# ethernet-phy.net
KiCad netlist of a schematic drawn in Altium Designer
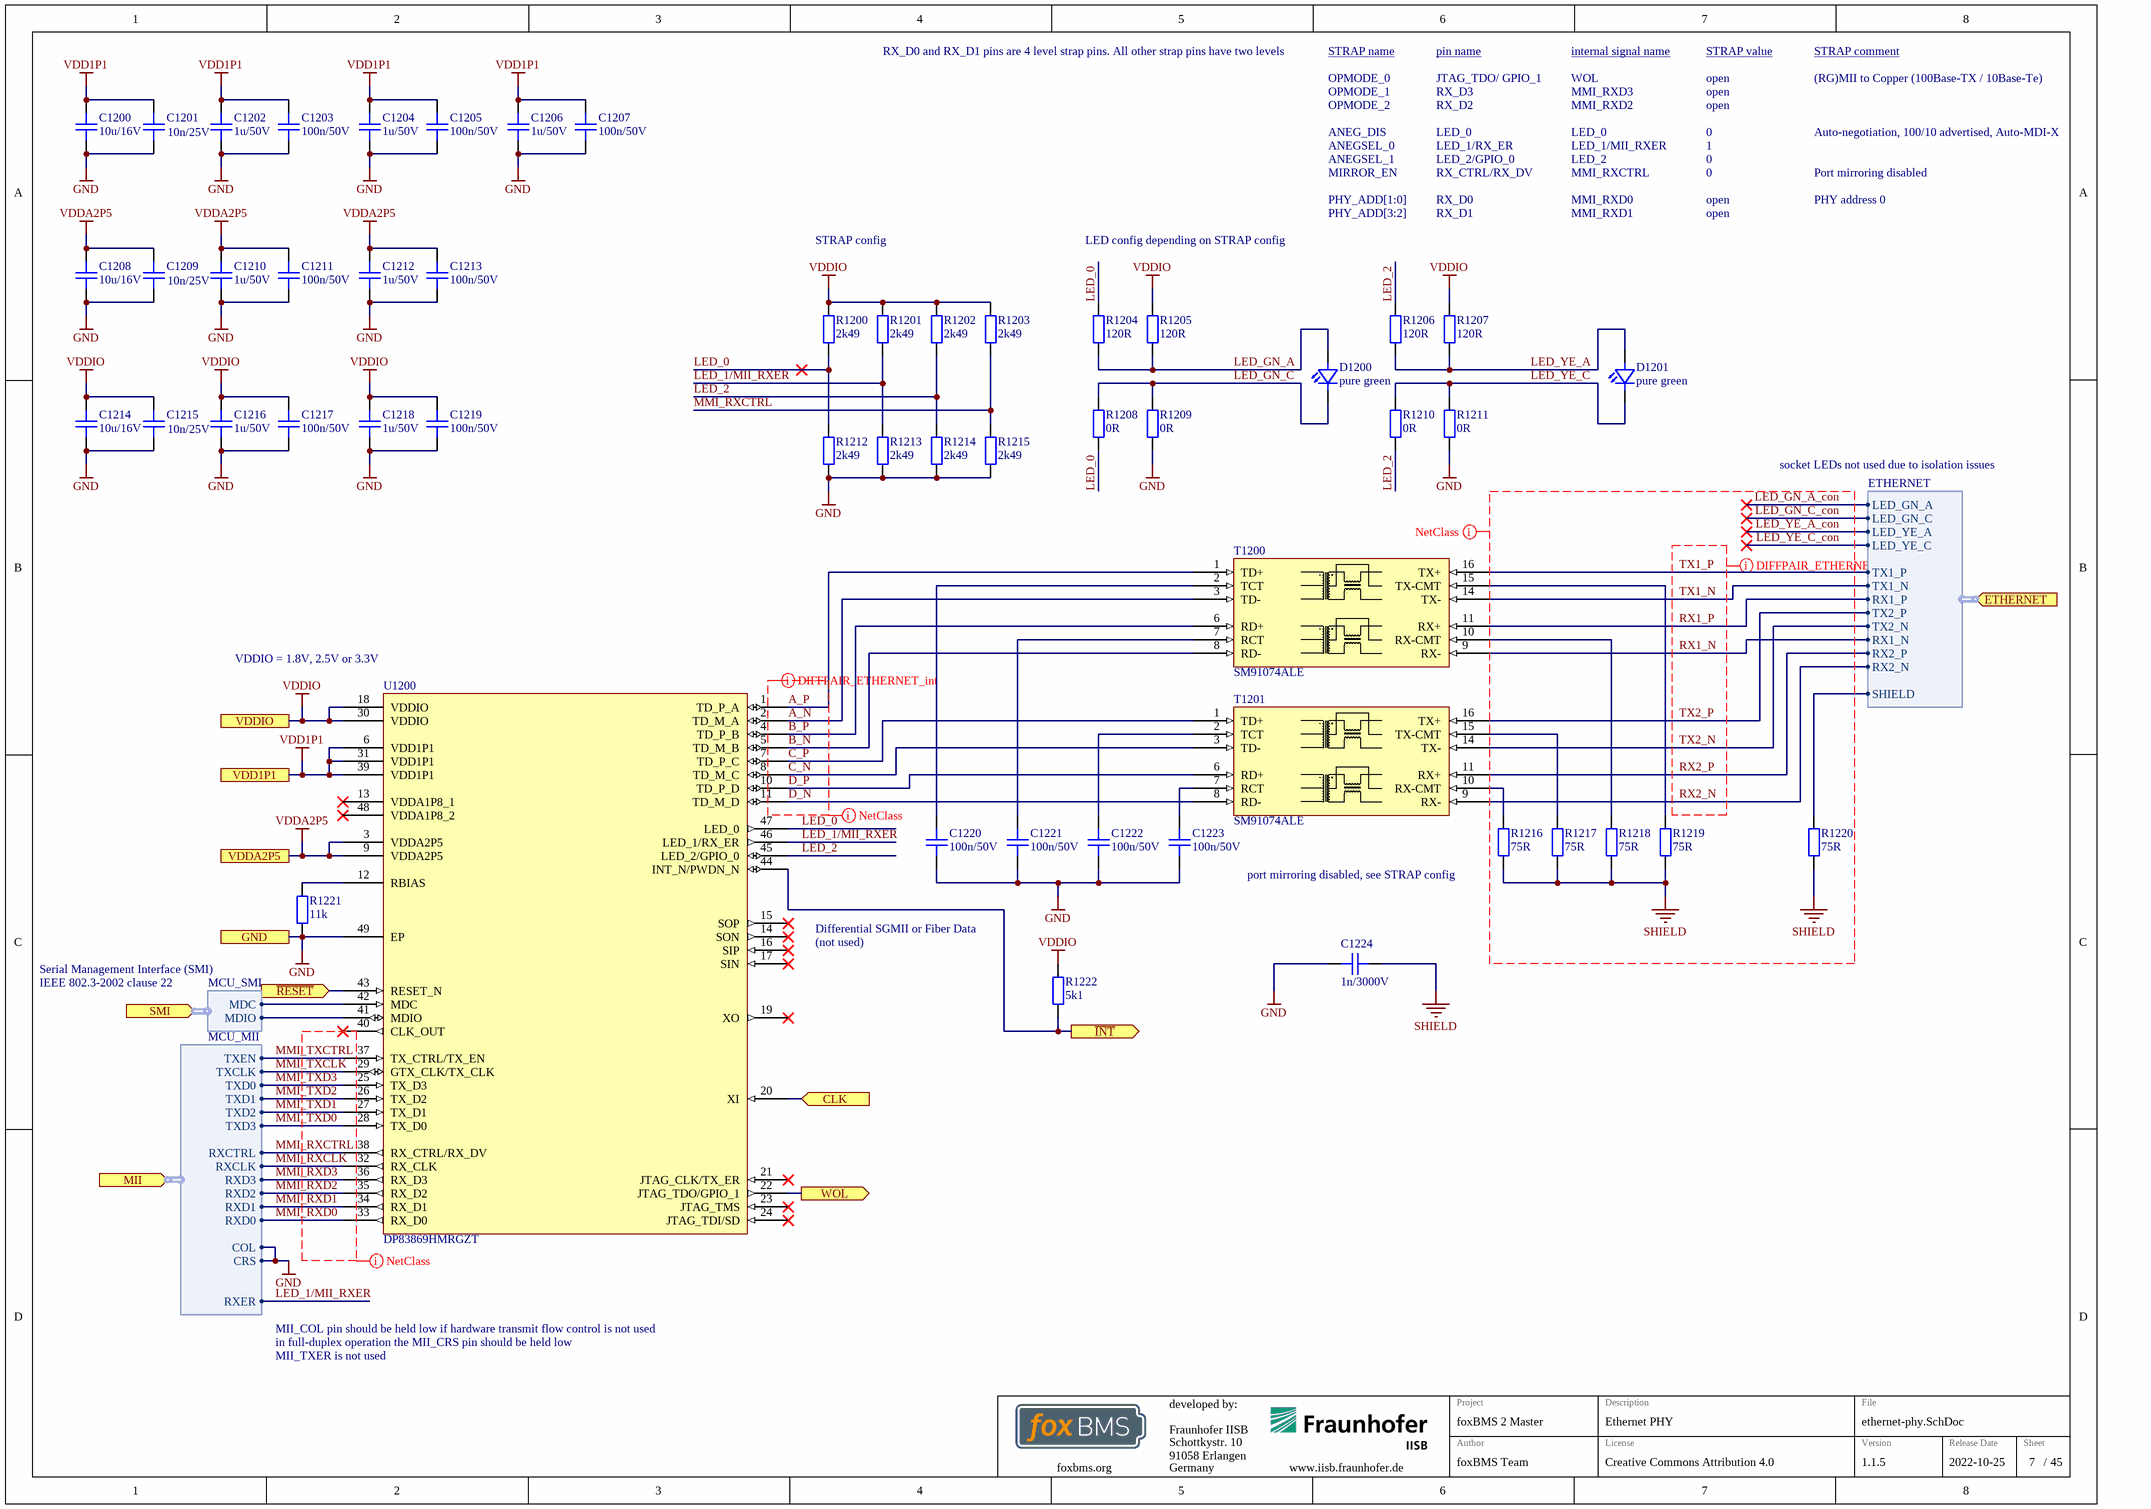
[diagram p0: ethernet-phy.SchDoc]

(export (version "E")
  (design (tool "Eeschema 10.0.6"))
  (components
    (comp (ref "C1200")
      (value "10u/16V")
      (footprint "CAPC2012X14N")
      (description "MLCC")
      (fields (field (name "PART NUMBER") "gen_C_ceramic_10u_16V_X7R_0805"))
      (libsource (lib "OE750") (part "C"))
    )
    (comp (ref "C1201")
      (value "10n/25V")
      (footprint "CAPC1005X06N")
      (description "MLCC")
      (fields (field (name "PART NUMBER") "gen_C_ceramic_10n_25V_X7R_0402"))
      (libsource (lib "OE750") (part "C"))
    )
    (comp (ref "C1202")
      (value "1u/50V")
      (footprint "CAPC1608X08N")
      (description "MLCC")
      (fields (field (name "PART NUMBER") "gen_C_ceramic_1u_50V_X7R_0603") (field (name "TOLERANCE") "± 10%"))
      (libsource (lib "OE750") (part "C"))
    )
    (comp (ref "C1203")
      (value "100n/50V")
      (footprint "CAPC1005X06N")
      (description "MLCC")
      (fields (field (name "PART NUMBER") "gen_C_ceramic_100n_50V_X7R_0402"))
      (libsource (lib "OE750") (part "C"))
    )
    (comp (ref "C1204")
      (value "1u/50V")
      (footprint "CAPC1608X08N")
      (description "MLCC")
      (fields (field (name "PART NUMBER") "gen_C_ceramic_1u_50V_X7R_0603") (field (name "TOLERANCE") "± 10%"))
      (libsource (lib "OE750") (part "C"))
    )
    (comp (ref "C1205")
      (value "100n/50V")
      (footprint "CAPC1005X06N")
      (description "MLCC")
      (fields (field (name "PART NUMBER") "gen_C_ceramic_100n_50V_X7R_0402"))
      (libsource (lib "OE750") (part "C"))
    )
    (comp (ref "C1206")
      (value "1u/50V")
      (footprint "CAPC1608X08N")
      (description "MLCC")
      (fields (field (name "PART NUMBER") "gen_C_ceramic_1u_50V_X7R_0603") (field (name "TOLERANCE") "± 10%"))
      (libsource (lib "OE750") (part "C"))
    )
    (comp (ref "C1207")
      (value "100n/50V")
      (footprint "CAPC1005X06N")
      (description "MLCC")
      (fields (field (name "PART NUMBER") "gen_C_ceramic_100n_50V_X7R_0402"))
      (libsource (lib "OE750") (part "C"))
    )
    (comp (ref "C1208")
      (value "10u/16V")
      (footprint "CAPC2012X14N")
      (description "MLCC")
      (fields (field (name "PART NUMBER") "gen_C_ceramic_10u_16V_X7R_0805"))
      (libsource (lib "OE750") (part "C"))
    )
    (comp (ref "C1209")
      (value "10n/25V")
      (footprint "CAPC1005X06N")
      (description "MLCC")
      (fields (field (name "PART NUMBER") "gen_C_ceramic_10n_25V_X7R_0402"))
      (libsource (lib "OE750") (part "C"))
    )
    (comp (ref "C1210")
      (value "1u/50V")
      (footprint "CAPC1608X08N")
      (description "MLCC")
      (fields (field (name "PART NUMBER") "gen_C_ceramic_1u_50V_X7R_0603") (field (name "TOLERANCE") "± 10%"))
      (libsource (lib "OE750") (part "C"))
    )
    (comp (ref "C1211")
      (value "100n/50V")
      (footprint "CAPC1005X06N")
      (description "MLCC")
      (fields (field (name "PART NUMBER") "gen_C_ceramic_100n_50V_X7R_0402"))
      (libsource (lib "OE750") (part "C"))
    )
    (comp (ref "C1212")
      (value "1u/50V")
      (footprint "CAPC1608X08N")
      (description "MLCC")
      (fields (field (name "PART NUMBER") "gen_C_ceramic_1u_50V_X7R_0603") (field (name "TOLERANCE") "± 10%"))
      (libsource (lib "OE750") (part "C"))
    )
    (comp (ref "C1213")
      (value "100n/50V")
      (footprint "CAPC1005X06N")
      (description "MLCC")
      (fields (field (name "PART NUMBER") "gen_C_ceramic_100n_50V_X7R_0402"))
      (libsource (lib "OE750") (part "C"))
    )
    (comp (ref "C1214")
      (value "10u/16V")
      (footprint "CAPC2012X14N")
      (description "MLCC")
      (fields (field (name "PART NUMBER") "gen_C_ceramic_10u_16V_X7R_0805"))
      (libsource (lib "OE750") (part "C"))
    )
    (comp (ref "C1215")
      (value "10n/25V")
      (footprint "CAPC1005X06N")
      (description "MLCC")
      (fields (field (name "PART NUMBER") "gen_C_ceramic_10n_25V_X7R_0402"))
      (libsource (lib "OE750") (part "C"))
    )
    (comp (ref "C1216")
      (value "1u/50V")
      (footprint "CAPC1608X08N")
      (description "MLCC")
      (fields (field (name "PART NUMBER") "gen_C_ceramic_1u_50V_X7R_0603") (field (name "TOLERANCE") "± 10%"))
      (libsource (lib "OE750") (part "C"))
    )
    (comp (ref "C1217")
      (value "100n/50V")
      (footprint "CAPC1005X06N")
      (description "MLCC")
      (fields (field (name "PART NUMBER") "gen_C_ceramic_100n_50V_X7R_0402"))
      (libsource (lib "OE750") (part "C"))
    )
    (comp (ref "C1218")
      (value "1u/50V")
      (footprint "CAPC1608X08N")
      (description "MLCC")
      (fields (field (name "PART NUMBER") "gen_C_ceramic_1u_50V_X7R_0603") (field (name "TOLERANCE") "± 10%"))
      (libsource (lib "OE750") (part "C"))
    )
    (comp (ref "C1219")
      (value "100n/50V")
      (footprint "CAPC1005X06N")
      (description "MLCC")
      (fields (field (name "PART NUMBER") "gen_C_ceramic_100n_50V_X7R_0402"))
      (libsource (lib "OE750") (part "C"))
    )
    (comp (ref "C1220")
      (value "100n/50V")
      (footprint "CAPC1005X06N")
      (description "MLCC")
      (fields (field (name "PART NUMBER") "gen_C_ceramic_100n_50V_X7R_0402"))
      (libsource (lib "OE750") (part "C"))
    )
    (comp (ref "C1221")
      (value "100n/50V")
      (footprint "CAPC1005X06N")
      (description "MLCC")
      (fields (field (name "PART NUMBER") "gen_C_ceramic_100n_50V_X7R_0402"))
      (libsource (lib "OE750") (part "C"))
    )
    (comp (ref "C1222")
      (value "100n/50V")
      (footprint "CAPC1005X06N")
      (description "MLCC")
      (fields (field (name "PART NUMBER") "gen_C_ceramic_100n_50V_X7R_0402"))
      (libsource (lib "OE750") (part "C"))
    )
    (comp (ref "C1223")
      (value "100n/50V")
      (footprint "CAPC1005X06N")
      (description "MLCC")
      (fields (field (name "PART NUMBER") "gen_C_ceramic_100n_50V_X7R_0402"))
      (libsource (lib "OE750") (part "C"))
    )
    (comp (ref "C1224")
      (value "1n/3000V")
      (footprint "CAPC2220(5750)230_N")
      (description "MLCC")
      (fields (field (name "PART NUMBER") "gen_C_ceramic_1n_3000V_X7R_2220"))
      (libsource (lib "OE750") (part "C"))
    )
    (comp (ref "D1200")
      (value "pure green")
      (footprint "LEDC1608X07N")
      (description "TLMP1100-GS08")
      (fields (field (name "PART NUMBER") "LED_0603_pure_green_AECQ") (field (name "MANUFACTURER") "Vishay"))
      (libsource (lib "OE750") (part "D_LED"))
    )
    (comp (ref "D1201")
      (value "pure green")
      (footprint "LEDC1608X07N")
      (description "TLMP1100-GS08")
      (fields (field (name "PART NUMBER") "LED_0603_pure_green_AECQ") (field (name "MANUFACTURER") "Vishay"))
      (libsource (lib "OE750") (part "D_LED"))
    )
    (comp (ref "R1200")
      (value "2k49")
      (footprint "RESC1005X04N")
      (description "SMD Resistor 2k49 0402")
      (fields (field (name "PART NUMBER") "gen_R_2k49_0402") (field (name "TOLERANCE") "1%"))
      (libsource (lib "OE750") (part "R"))
    )
    (comp (ref "R1201")
      (value "2k49")
      (footprint "RESC1005X04N")
      (description "SMD Resistor 2k49 0402")
      (fields (field (name "PART NUMBER") "gen_R_2k49_0402") (field (name "TOLERANCE") "1%"))
      (libsource (lib "OE750") (part "R"))
    )
    (comp (ref "R1202")
      (value "2k49")
      (footprint "RESC1005X04N")
      (description "SMD Resistor 2k49 0402")
      (fields (field (name "PART NUMBER") "gen_R_2k49_0402") (field (name "TOLERANCE") "1%"))
      (libsource (lib "OE750") (part "R"))
    )
    (comp (ref "R1203")
      (value "2k49")
      (footprint "RESC1005X04N")
      (description "SMD Resistor 2k49 0402")
      (fields (field (name "PART NUMBER") "gen_R_2k49_0402") (field (name "TOLERANCE") "1%"))
      (libsource (lib "OE750") (part "R"))
    )
    (comp (ref "R1204")
      (value "120R")
      (footprint "RESC1005X04N")
      (description "SMD Resistor 120R 0402")
      (fields (field (name "PART NUMBER") "gen_R_120R_0402") (field (name "TOLERANCE") "1%"))
      (libsource (lib "OE750") (part "R"))
    )
    (comp (ref "R1205")
      (value "120R")
      (footprint "RESC1005X04N")
      (description "SMD Resistor 120R 0402")
      (fields (field (name "PART NUMBER") "gen_R_120R_0402") (field (name "TOLERANCE") "1%"))
      (libsource (lib "OE750") (part "R"))
    )
    (comp (ref "R1206")
      (value "120R")
      (footprint "RESC1005X04N")
      (description "SMD Resistor 120R 0402")
      (fields (field (name "PART NUMBER") "gen_R_120R_0402") (field (name "TOLERANCE") "1%"))
      (libsource (lib "OE750") (part "R"))
    )
    (comp (ref "R1207")
      (value "120R")
      (footprint "RESC1005X04N")
      (description "SMD Resistor 120R 0402")
      (fields (field (name "PART NUMBER") "gen_R_120R_0402") (field (name "TOLERANCE") "1%"))
      (libsource (lib "OE750") (part "R"))
    )
    (comp (ref "R1208")
      (value "0R")
      (footprint "RESC1005X04N")
      (description "SMD Resistor 0R 0402")
      (fields (field (name "PART NUMBER") "gen_R_0R_0402") (field (name "POWER") "0.063W"))
      (libsource (lib "OE750") (part "R"))
    )
    (comp (ref "R1209")
      (value "0R")
      (footprint "RESC1005X04N")
      (description "SMD Resistor 0R 0402")
      (fields (field (name "PART NUMBER") "gen_R_0R_0402") (field (name "POWER") "0.063W"))
      (libsource (lib "OE750") (part "R"))
    )
    (comp (ref "R1210")
      (value "0R")
      (footprint "RESC1005X04N")
      (description "SMD Resistor 0R 0402")
      (fields (field (name "PART NUMBER") "gen_R_0R_0402") (field (name "POWER") "0.063W"))
      (libsource (lib "OE750") (part "R"))
    )
    (comp (ref "R1211")
      (value "0R")
      (footprint "RESC1005X04N")
      (description "SMD Resistor 0R 0402")
      (fields (field (name "PART NUMBER") "gen_R_0R_0402") (field (name "POWER") "0.063W"))
      (libsource (lib "OE750") (part "R"))
    )
    (comp (ref "R1212")
      (value "2k49")
      (footprint "RESC1005X04N")
      (description "SMD Resistor 2k49 0402")
      (fields (field (name "PART NUMBER") "gen_R_2k49_0402") (field (name "TOLERANCE") "1%"))
      (libsource (lib "OE750") (part "R"))
    )
    (comp (ref "R1213")
      (value "2k49")
      (footprint "RESC1005X04N")
      (description "SMD Resistor 2k49 0402")
      (fields (field (name "PART NUMBER") "gen_R_2k49_0402") (field (name "TOLERANCE") "1%"))
      (libsource (lib "OE750") (part "R"))
    )
    (comp (ref "R1214")
      (value "2k49")
      (footprint "RESC1005X04N")
      (description "SMD Resistor 2k49 0402")
      (fields (field (name "PART NUMBER") "gen_R_2k49_0402") (field (name "TOLERANCE") "1%"))
      (libsource (lib "OE750") (part "R"))
    )
    (comp (ref "R1215")
      (value "2k49")
      (footprint "RESC1005X04N")
      (description "SMD Resistor 2k49 0402")
      (fields (field (name "PART NUMBER") "gen_R_2k49_0402") (field (name "TOLERANCE") "1%"))
      (libsource (lib "OE750") (part "R"))
    )
    (comp (ref "R1216")
      (value "75R")
      (footprint "RESC1005X04N")
      (description "SMD Resistor 75R 0402")
      (fields (field (name "PART NUMBER") "gen_R_75R_0402") (field (name "TOLERANCE") "1%"))
      (libsource (lib "OE750") (part "R"))
    )
    (comp (ref "R1217")
      (value "75R")
      (footprint "RESC1005X04N")
      (description "SMD Resistor 75R 0402")
      (fields (field (name "PART NUMBER") "gen_R_75R_0402") (field (name "TOLERANCE") "1%"))
      (libsource (lib "OE750") (part "R"))
    )
    (comp (ref "R1218")
      (value "75R")
      (footprint "RESC1005X04N")
      (description "SMD Resistor 75R 0402")
      (fields (field (name "PART NUMBER") "gen_R_75R_0402") (field (name "TOLERANCE") "1%"))
      (libsource (lib "OE750") (part "R"))
    )
    (comp (ref "R1219")
      (value "75R")
      (footprint "RESC1005X04N")
      (description "SMD Resistor 75R 0402")
      (fields (field (name "PART NUMBER") "gen_R_75R_0402") (field (name "TOLERANCE") "1%"))
      (libsource (lib "OE750") (part "R"))
    )
    (comp (ref "R1220")
      (value "75R")
      (footprint "RESC1005X04N")
      (description "SMD Resistor 75R 0402")
      (fields (field (name "PART NUMBER") "gen_R_75R_0402") (field (name "TOLERANCE") "1%"))
      (libsource (lib "OE750") (part "R"))
    )
    (comp (ref "R1221")
      (value "11k")
      (footprint "RESC1005X04N")
      (description "SMD Resistor 11k 0402")
      (fields (field (name "PART NUMBER") "gen_R_11k_0402") (field (name "TOLERANCE") "1%"))
      (libsource (lib "OE750") (part "R"))
    )
    (comp (ref "R1222")
      (value "5k1")
      (footprint "RESC1005X04N")
      (description "SMD Resistor 5k1 0402")
      (fields (field (name "PART NUMBER") "gen_R_5k1_0402") (field (name "TOLERANCE") "1%"))
      (libsource (lib "OE750") (part "R"))
    )
    (comp (ref "T1200")
      (value "SM91074ALE")
      (footprint "SM91074ALE")
      (description "10/100 Base-T Transformer")
      (fields (field (name "MANUFACTURER") "Bourns"))
      (libsource (lib "OE750") (part "SM91074ALE"))
    )
    (comp (ref "T1201")
      (value "SM91074ALE")
      (footprint "SM91074ALE")
      (description "10/100 Base-T Transformer")
      (fields (field (name "MANUFACTURER") "Bourns"))
      (libsource (lib "OE750") (part "SM91074ALE"))
    )
    (comp (ref "U1200")
      (value "DP83869HMRGZT")
      (footprint "DP83869HM-RGZ")
      (description "High Immunity 10/100/1000 Ethernet Physical Layer Transceiver and Fiber Interface")
      (fields (field (name "MANUFACTURER") "Texas Instruments"))
      (libsource (lib "OE750") (part "DP83869HM"))
    )
  )
  (nets
    (net (code "4") (name "/A_N") (class "Default")
      (node (ref "T1200") (pin "3") (pinfunction "TD-_3") (pintype "input"))
      (node (ref "U1200") (pin "2") (pinfunction "TD_M_A_2") (pintype "bidirectional"))
    )
    (net (code "5") (name "/A_P") (class "Default")
      (node (ref "T1200") (pin "1") (pinfunction "TD+_1") (pintype "input"))
      (node (ref "U1200") (pin "1") (pinfunction "TD_P_A_1") (pintype "bidirectional"))
    )
    (net (code "6") (name "/B_N") (class "Default")
      (node (ref "T1200") (pin "8") (pinfunction "RD-_8") (pintype "input"))
      (node (ref "U1200") (pin "5") (pinfunction "TD_M_B_5") (pintype "bidirectional"))
    )
    (net (code "7") (name "/B_P") (class "Default")
      (node (ref "T1200") (pin "6") (pinfunction "RD+_6") (pintype "input"))
      (node (ref "U1200") (pin "4") (pinfunction "TD_P_B_4") (pintype "bidirectional"))
    )
    (net (code "8") (name "/CLK") (class "Default")
      (node (ref "U1200") (pin "20") (pinfunction "XI_20") (pintype "input"))
    )
    (net (code "9") (name "/C_N") (class "Default")
      (node (ref "T1201") (pin "3") (pinfunction "TD-_3") (pintype "input"))
      (node (ref "U1200") (pin "8") (pinfunction "TD_M_C_8") (pintype "bidirectional"))
    )
    (net (code "10") (name "/C_P") (class "Default")
      (node (ref "T1201") (pin "1") (pinfunction "TD+_1") (pintype "input"))
      (node (ref "U1200") (pin "7") (pinfunction "TD_P_C_7") (pintype "bidirectional"))
    )
    (net (code "11") (name "/D_N") (class "Default")
      (node (ref "T1201") (pin "8") (pinfunction "RD-_8") (pintype "input"))
      (node (ref "U1200") (pin "11") (pinfunction "TD_M_D_11") (pintype "bidirectional"))
    )
    (net (code "12") (name "/D_P") (class "Default")
      (node (ref "T1201") (pin "6") (pinfunction "RD+_6") (pintype "input"))
      (node (ref "U1200") (pin "10") (pinfunction "TD_P_D_10") (pintype "bidirectional"))
    )
    (net (code "13") (name "/INT") (class "Default")
      (node (ref "R1222") (pin "1") (pinfunction "1_1") (pintype "passive"))
      (node (ref "U1200") (pin "44") (pinfunction "INT_N/PWDN_N_44") (pintype "bidirectional"))
    )
    (net (code "14") (name "/LED_0") (class "Default")
      (node (ref "R1200") (pin "1") (pinfunction "1_1") (pintype "passive"))
      (node (ref "R1204") (pin "2") (pinfunction "2_2") (pintype "passive"))
      (node (ref "R1208") (pin "1") (pinfunction "1_1") (pintype "passive"))
      (node (ref "R1212") (pin "2") (pinfunction "2_2") (pintype "passive"))
      (node (ref "U1200") (pin "47") (pinfunction "LED_0_47") (pintype "output"))
    )
    (net (code "15") (name "/LED_1{slash}MII_RXER") (class "Default")
      (node (ref "R1201") (pin "1") (pinfunction "1_1") (pintype "passive"))
      (node (ref "R1213") (pin "2") (pinfunction "2_2") (pintype "passive"))
      (node (ref "U1200") (pin "46") (pinfunction "LED_1/RX_ER_46") (pintype "output"))
    )
    (net (code "16") (name "/LED_2") (class "Default")
      (node (ref "R1202") (pin "1") (pinfunction "1_1") (pintype "passive"))
      (node (ref "R1206") (pin "2") (pinfunction "2_2") (pintype "passive"))
      (node (ref "R1210") (pin "1") (pinfunction "1_1") (pintype "passive"))
      (node (ref "R1214") (pin "2") (pinfunction "2_2") (pintype "passive"))
      (node (ref "U1200") (pin "45") (pinfunction "LED_2/GPIO_0_45") (pintype "bidirectional"))
    )
    (net (code "17") (name "/LED_GN_A") (class "Default")
      (node (ref "D1200") (pin "2") (pinfunction "A_2") (pintype "passive"))
      (node (ref "R1204") (pin "1") (pinfunction "1_1") (pintype "passive"))
      (node (ref "R1205") (pin "1") (pinfunction "1_1") (pintype "passive"))
    )
    (net (code "19") (name "/LED_GN_C") (class "Default")
      (node (ref "D1200") (pin "1") (pinfunction "C_1") (pintype "passive"))
      (node (ref "R1208") (pin "2") (pinfunction "2_2") (pintype "passive"))
      (node (ref "R1209") (pin "2") (pinfunction "2_2") (pintype "passive"))
    )
    (net (code "21") (name "/LED_YE_A") (class "Default")
      (node (ref "D1201") (pin "2") (pinfunction "A_2") (pintype "passive"))
      (node (ref "R1206") (pin "1") (pinfunction "1_1") (pintype "passive"))
      (node (ref "R1207") (pin "1") (pinfunction "1_1") (pintype "passive"))
    )
    (net (code "23") (name "/LED_YE_C") (class "Default")
      (node (ref "D1201") (pin "1") (pinfunction "C_1") (pintype "passive"))
      (node (ref "R1210") (pin "2") (pinfunction "2_2") (pintype "passive"))
      (node (ref "R1211") (pin "2") (pinfunction "2_2") (pintype "passive"))
    )
    (net (code "25") (name "/MDC") (class "Default")
      (node (ref "U1200") (pin "42") (pinfunction "MDC_42") (pintype "input"))
    )
    (net (code "26") (name "/MDIO") (class "Default")
      (node (ref "U1200") (pin "41") (pinfunction "MDIO_41") (pintype "bidirectional"))
    )
    (net (code "27") (name "/MMI_RXCLK") (class "Default")
      (node (ref "U1200") (pin "32") (pinfunction "RX_CLK_32") (pintype "output"))
    )
    (net (code "28") (name "/MMI_RXCTRL") (class "Default")
      (node (ref "R1203") (pin "1") (pinfunction "1_1") (pintype "passive"))
      (node (ref "R1215") (pin "2") (pinfunction "2_2") (pintype "passive"))
      (node (ref "U1200") (pin "38") (pinfunction "RX_CTRL/RX_DV_38") (pintype "output"))
    )
    (net (code "29") (name "/MMI_RXD0") (class "Default")
      (node (ref "U1200") (pin "33") (pinfunction "RX_D0_33") (pintype "output"))
    )
    (net (code "30") (name "/MMI_RXD1") (class "Default")
      (node (ref "U1200") (pin "34") (pinfunction "RX_D1_34") (pintype "output"))
    )
    (net (code "31") (name "/MMI_RXD2") (class "Default")
      (node (ref "U1200") (pin "35") (pinfunction "RX_D2_35") (pintype "output"))
    )
    (net (code "32") (name "/MMI_RXD3") (class "Default")
      (node (ref "U1200") (pin "36") (pinfunction "RX_D3_36") (pintype "output"))
    )
    (net (code "33") (name "/MMI_TXCLK") (class "Default")
      (node (ref "U1200") (pin "29") (pinfunction "GTX_CLK/TX_CLK_29") (pintype "bidirectional"))
    )
    (net (code "34") (name "/MMI_TXCTRL") (class "Default")
      (node (ref "U1200") (pin "37") (pinfunction "TX_CTRL/TX_EN_37") (pintype "input"))
    )
    (net (code "35") (name "/MMI_TXD0") (class "Default")
      (node (ref "U1200") (pin "28") (pinfunction "TX_D0_28") (pintype "input"))
    )
    (net (code "36") (name "/MMI_TXD1") (class "Default")
      (node (ref "U1200") (pin "27") (pinfunction "TX_D1_27") (pintype "input"))
    )
    (net (code "37") (name "/MMI_TXD2") (class "Default")
      (node (ref "U1200") (pin "26") (pinfunction "TX_D2_26") (pintype "input"))
    )
    (net (code "38") (name "/MMI_TXD3") (class "Default")
      (node (ref "U1200") (pin "25") (pinfunction "TX_D3_25") (pintype "input"))
    )
    (net (code "39") (name "/RESET") (class "Default")
      (node (ref "U1200") (pin "43") (pinfunction "RESET_N_43") (pintype "input"))
    )
    (net (code "40") (name "/RX1_N") (class "Default")
      (node (ref "T1200") (pin "9") (pinfunction "RX-_9") (pintype "input"))
    )
    (net (code "41") (name "/RX1_P") (class "Default")
      (node (ref "T1200") (pin "11") (pinfunction "RX+_11") (pintype "input"))
    )
    (net (code "42") (name "/RX2_N") (class "Default")
      (node (ref "T1201") (pin "9") (pinfunction "RX-_9") (pintype "input"))
    )
    (net (code "43") (name "/RX2_P") (class "Default")
      (node (ref "T1201") (pin "11") (pinfunction "RX+_11") (pintype "input"))
    )
    (net (code "44") (name "/TX1_N") (class "Default")
      (node (ref "T1200") (pin "14") (pinfunction "TX-_14") (pintype "input"))
    )
    (net (code "45") (name "/TX1_P") (class "Default")
      (node (ref "T1200") (pin "16") (pinfunction "TX+_16") (pintype "input"))
    )
    (net (code "46") (name "/TX2_N") (class "Default")
      (node (ref "T1201") (pin "14") (pinfunction "TX-_14") (pintype "input"))
    )
    (net (code "47") (name "/TX2_P") (class "Default")
      (node (ref "T1201") (pin "16") (pinfunction "TX+_16") (pintype "input"))
    )
    (net (code "48") (name "/WOL") (class "Default")
      (node (ref "U1200") (pin "22") (pinfunction "JTAG_TDO/GPIO_1_22") (pintype "output"))
    )
    (net (code "52") (name "GND") (class "Default")
      (node (ref "C1200") (pin "1") (pinfunction "1_1") (pintype "passive"))
      (node (ref "C1201") (pin "1") (pinfunction "1_1") (pintype "passive"))
      (node (ref "C1202") (pin "1") (pinfunction "1_1") (pintype "passive"))
      (node (ref "C1203") (pin "1") (pinfunction "1_1") (pintype "passive"))
      (node (ref "C1204") (pin "1") (pinfunction "1_1") (pintype "passive"))
      (node (ref "C1205") (pin "1") (pinfunction "1_1") (pintype "passive"))
      (node (ref "C1206") (pin "1") (pinfunction "1_1") (pintype "passive"))
      (node (ref "C1207") (pin "1") (pinfunction "1_1") (pintype "passive"))
      (node (ref "C1208") (pin "1") (pinfunction "1_1") (pintype "passive"))
      (node (ref "C1209") (pin "1") (pinfunction "1_1") (pintype "passive"))
      (node (ref "C1210") (pin "1") (pinfunction "1_1") (pintype "passive"))
      (node (ref "C1211") (pin "1") (pinfunction "1_1") (pintype "passive"))
      (node (ref "C1212") (pin "1") (pinfunction "1_1") (pintype "passive"))
      (node (ref "C1213") (pin "1") (pinfunction "1_1") (pintype "passive"))
      (node (ref "C1214") (pin "1") (pinfunction "1_1") (pintype "passive"))
      (node (ref "C1215") (pin "1") (pinfunction "1_1") (pintype "passive"))
      (node (ref "C1216") (pin "1") (pinfunction "1_1") (pintype "passive"))
      (node (ref "C1217") (pin "1") (pinfunction "1_1") (pintype "passive"))
      (node (ref "C1218") (pin "1") (pinfunction "1_1") (pintype "passive"))
      (node (ref "C1219") (pin "1") (pinfunction "1_1") (pintype "passive"))
      (node (ref "C1220") (pin "1") (pinfunction "1_1") (pintype "passive"))
      (node (ref "C1221") (pin "1") (pinfunction "1_1") (pintype "passive"))
      (node (ref "C1222") (pin "1") (pinfunction "1_1") (pintype "passive"))
      (node (ref "C1223") (pin "1") (pinfunction "1_1") (pintype "passive"))
      (node (ref "C1224") (pin "1") (pinfunction "1_1") (pintype "passive"))
      (node (ref "R1209") (pin "1") (pinfunction "1_1") (pintype "passive"))
      (node (ref "R1211") (pin "1") (pinfunction "1_1") (pintype "passive"))
      (node (ref "R1212") (pin "1") (pinfunction "1_1") (pintype "passive"))
      (node (ref "R1213") (pin "1") (pinfunction "1_1") (pintype "passive"))
      (node (ref "R1214") (pin "1") (pinfunction "1_1") (pintype "passive"))
      (node (ref "R1215") (pin "1") (pinfunction "1_1") (pintype "passive"))
      (node (ref "R1221") (pin "1") (pinfunction "1_1") (pintype "passive"))
      (node (ref "U1200") (pin "49") (pinfunction "EP_49") (pintype "power_in"))
    )
    (net (code "53") (name "Net-(T1200-RCT)") (class "Default")
      (node (ref "C1221") (pin "2") (pinfunction "2_2") (pintype "passive"))
      (node (ref "T1200") (pin "7") (pinfunction "RCT_7") (pintype "input"))
    )
    (net (code "54") (name "Net-(T1200-RX-CMT)") (class "Default")
      (node (ref "R1218") (pin "2") (pinfunction "2_2") (pintype "passive"))
      (node (ref "T1200") (pin "10") (pinfunction "RX-CMT_10") (pintype "input"))
    )
    (net (code "55") (name "Net-(T1200-TCT)") (class "Default")
      (node (ref "C1220") (pin "2") (pinfunction "2_2") (pintype "passive"))
      (node (ref "T1200") (pin "2") (pinfunction "TCT_2") (pintype "input"))
    )
    (net (code "56") (name "Net-(T1200-TX-CMT)") (class "Default")
      (node (ref "R1219") (pin "2") (pinfunction "2_2") (pintype "passive"))
      (node (ref "T1200") (pin "15") (pinfunction "TX-CMT_15") (pintype "input"))
    )
    (net (code "57") (name "Net-(T1201-RCT)") (class "Default")
      (node (ref "C1223") (pin "2") (pinfunction "2_2") (pintype "passive"))
      (node (ref "T1201") (pin "7") (pinfunction "RCT_7") (pintype "input"))
    )
    (net (code "58") (name "Net-(T1201-RX-CMT)") (class "Default")
      (node (ref "R1216") (pin "2") (pinfunction "2_2") (pintype "passive"))
      (node (ref "T1201") (pin "10") (pinfunction "RX-CMT_10") (pintype "input"))
    )
    (net (code "59") (name "Net-(T1201-TCT)") (class "Default")
      (node (ref "C1222") (pin "2") (pinfunction "2_2") (pintype "passive"))
      (node (ref "T1201") (pin "2") (pinfunction "TCT_2") (pintype "input"))
    )
    (net (code "60") (name "Net-(T1201-TX-CMT)") (class "Default")
      (node (ref "R1217") (pin "2") (pinfunction "2_2") (pintype "passive"))
      (node (ref "T1201") (pin "15") (pinfunction "TX-CMT_15") (pintype "input"))
    )
    (net (code "61") (name "Net-(U1200-RBIAS)") (class "Default")
      (node (ref "R1221") (pin "2") (pinfunction "2_2") (pintype "passive"))
      (node (ref "U1200") (pin "12") (pinfunction "RBIAS_12") (pintype "passive"))
    )
    (net (code "62") (name "SHIELD") (class "Default")
      (node (ref "C1224") (pin "2") (pinfunction "2_2") (pintype "passive"))
      (node (ref "R1216") (pin "1") (pinfunction "1_1") (pintype "passive"))
      (node (ref "R1217") (pin "1") (pinfunction "1_1") (pintype "passive"))
      (node (ref "R1218") (pin "1") (pinfunction "1_1") (pintype "passive"))
      (node (ref "R1219") (pin "1") (pinfunction "1_1") (pintype "passive"))
      (node (ref "R1220") (pin "1") (pinfunction "1_1") (pintype "passive"))
    )
    (net (code "63") (name "VDD1P1") (class "Default")
      (node (ref "C1200") (pin "2") (pinfunction "2_2") (pintype "passive"))
      (node (ref "C1201") (pin "2") (pinfunction "2_2") (pintype "passive"))
      (node (ref "C1202") (pin "2") (pinfunction "2_2") (pintype "passive"))
      (node (ref "C1203") (pin "2") (pinfunction "2_2") (pintype "passive"))
      (node (ref "C1204") (pin "2") (pinfunction "2_2") (pintype "passive"))
      (node (ref "C1205") (pin "2") (pinfunction "2_2") (pintype "passive"))
      (node (ref "C1206") (pin "2") (pinfunction "2_2") (pintype "passive"))
      (node (ref "C1207") (pin "2") (pinfunction "2_2") (pintype "passive"))
      (node (ref "U1200") (pin "31") (pinfunction "VDD1P1_31") (pintype "power_in"))
      (node (ref "U1200") (pin "39") (pinfunction "VDD1P1_39") (pintype "power_in"))
      (node (ref "U1200") (pin "6") (pinfunction "VDD1P1_6") (pintype "power_in"))
    )
    (net (code "64") (name "VDDA2P5") (class "Default")
      (node (ref "C1208") (pin "2") (pinfunction "2_2") (pintype "passive"))
      (node (ref "C1209") (pin "2") (pinfunction "2_2") (pintype "passive"))
      (node (ref "C1210") (pin "2") (pinfunction "2_2") (pintype "passive"))
      (node (ref "C1211") (pin "2") (pinfunction "2_2") (pintype "passive"))
      (node (ref "C1212") (pin "2") (pinfunction "2_2") (pintype "passive"))
      (node (ref "C1213") (pin "2") (pinfunction "2_2") (pintype "passive"))
      (node (ref "U1200") (pin "3") (pinfunction "VDDA2P5_3") (pintype "power_in"))
      (node (ref "U1200") (pin "9") (pinfunction "VDDA2P5_9") (pintype "power_in"))
    )
    (net (code "65") (name "VDDIO") (class "Default")
      (node (ref "C1214") (pin "2") (pinfunction "2_2") (pintype "passive"))
      (node (ref "C1215") (pin "2") (pinfunction "2_2") (pintype "passive"))
      (node (ref "C1216") (pin "2") (pinfunction "2_2") (pintype "passive"))
      (node (ref "C1217") (pin "2") (pinfunction "2_2") (pintype "passive"))
      (node (ref "C1218") (pin "2") (pinfunction "2_2") (pintype "passive"))
      (node (ref "C1219") (pin "2") (pinfunction "2_2") (pintype "passive"))
      (node (ref "R1200") (pin "2") (pinfunction "2_2") (pintype "passive"))
      (node (ref "R1201") (pin "2") (pinfunction "2_2") (pintype "passive"))
      (node (ref "R1202") (pin "2") (pinfunction "2_2") (pintype "passive"))
      (node (ref "R1203") (pin "2") (pinfunction "2_2") (pintype "passive"))
      (node (ref "R1205") (pin "2") (pinfunction "2_2") (pintype "passive"))
      (node (ref "R1207") (pin "2") (pinfunction "2_2") (pintype "passive"))
      (node (ref "R1222") (pin "2") (pinfunction "2_2") (pintype "passive"))
      (node (ref "U1200") (pin "18") (pinfunction "VDDIO_18") (pintype "power_in"))
      (node (ref "U1200") (pin "30") (pinfunction "VDDIO_30") (pintype "power_in"))
    )
    (net (code "66") (name "unconnected-(R1220-Pad2)") (class "Default")
      (node (ref "R1220") (pin "2") (pinfunction "2_2") (pintype "passive"))
    )
    (net (code "67") (name "unconnected-(U1200-CLK_OUT-Pad40)") (class "Default")
      (node (ref "U1200") (pin "40") (pinfunction "CLK_OUT_40") (pintype "output+no_connect"))
    )
    (net (code "68") (name "unconnected-(U1200-JTAG_CLK{slash}TX_ER-Pad21)") (class "Default")
      (node (ref "U1200") (pin "21") (pinfunction "JTAG_CLK/TX_ER_21") (pintype "input+no_connect"))
    )
    (net (code "69") (name "unconnected-(U1200-JTAG_TDI{slash}SD-Pad24)") (class "Default")
      (node (ref "U1200") (pin "24") (pinfunction "JTAG_TDI/SD_24") (pintype "input+no_connect"))
    )
    (net (code "70") (name "unconnected-(U1200-JTAG_TMS-Pad23)") (class "Default")
      (node (ref "U1200") (pin "23") (pinfunction "JTAG_TMS_23") (pintype "input+no_connect"))
    )
    (net (code "71") (name "unconnected-(U1200-SIN-Pad17)") (class "Default")
      (node (ref "U1200") (pin "17") (pinfunction "SIN_17") (pintype "input+no_connect"))
    )
    (net (code "72") (name "unconnected-(U1200-SIP-Pad16)") (class "Default")
      (node (ref "U1200") (pin "16") (pinfunction "SIP_16") (pintype "input+no_connect"))
    )
    (net (code "73") (name "unconnected-(U1200-SON-Pad14)") (class "Default")
      (node (ref "U1200") (pin "14") (pinfunction "SON_14") (pintype "output+no_connect"))
    )
    (net (code "74") (name "unconnected-(U1200-SOP-Pad15)") (class "Default")
      (node (ref "U1200") (pin "15") (pinfunction "SOP_15") (pintype "output+no_connect"))
    )
    (net (code "75") (name "unconnected-(U1200-VDDA1P8_1-Pad13)") (class "Default")
      (node (ref "U1200") (pin "13") (pinfunction "VDDA1P8_1_13") (pintype "power_in+no_connect"))
    )
    (net (code "76") (name "unconnected-(U1200-VDDA1P8_2-Pad48)") (class "Default")
      (node (ref "U1200") (pin "48") (pinfunction "VDDA1P8_2_48") (pintype "power_in+no_connect"))
    )
    (net (code "77") (name "unconnected-(U1200-XO-Pad19)") (class "Default")
      (node (ref "U1200") (pin "19") (pinfunction "XO_19") (pintype "output+no_connect"))
    )
  )
)
